# Main.net
KiCad netlist of a schematic drawn in Altium Designer
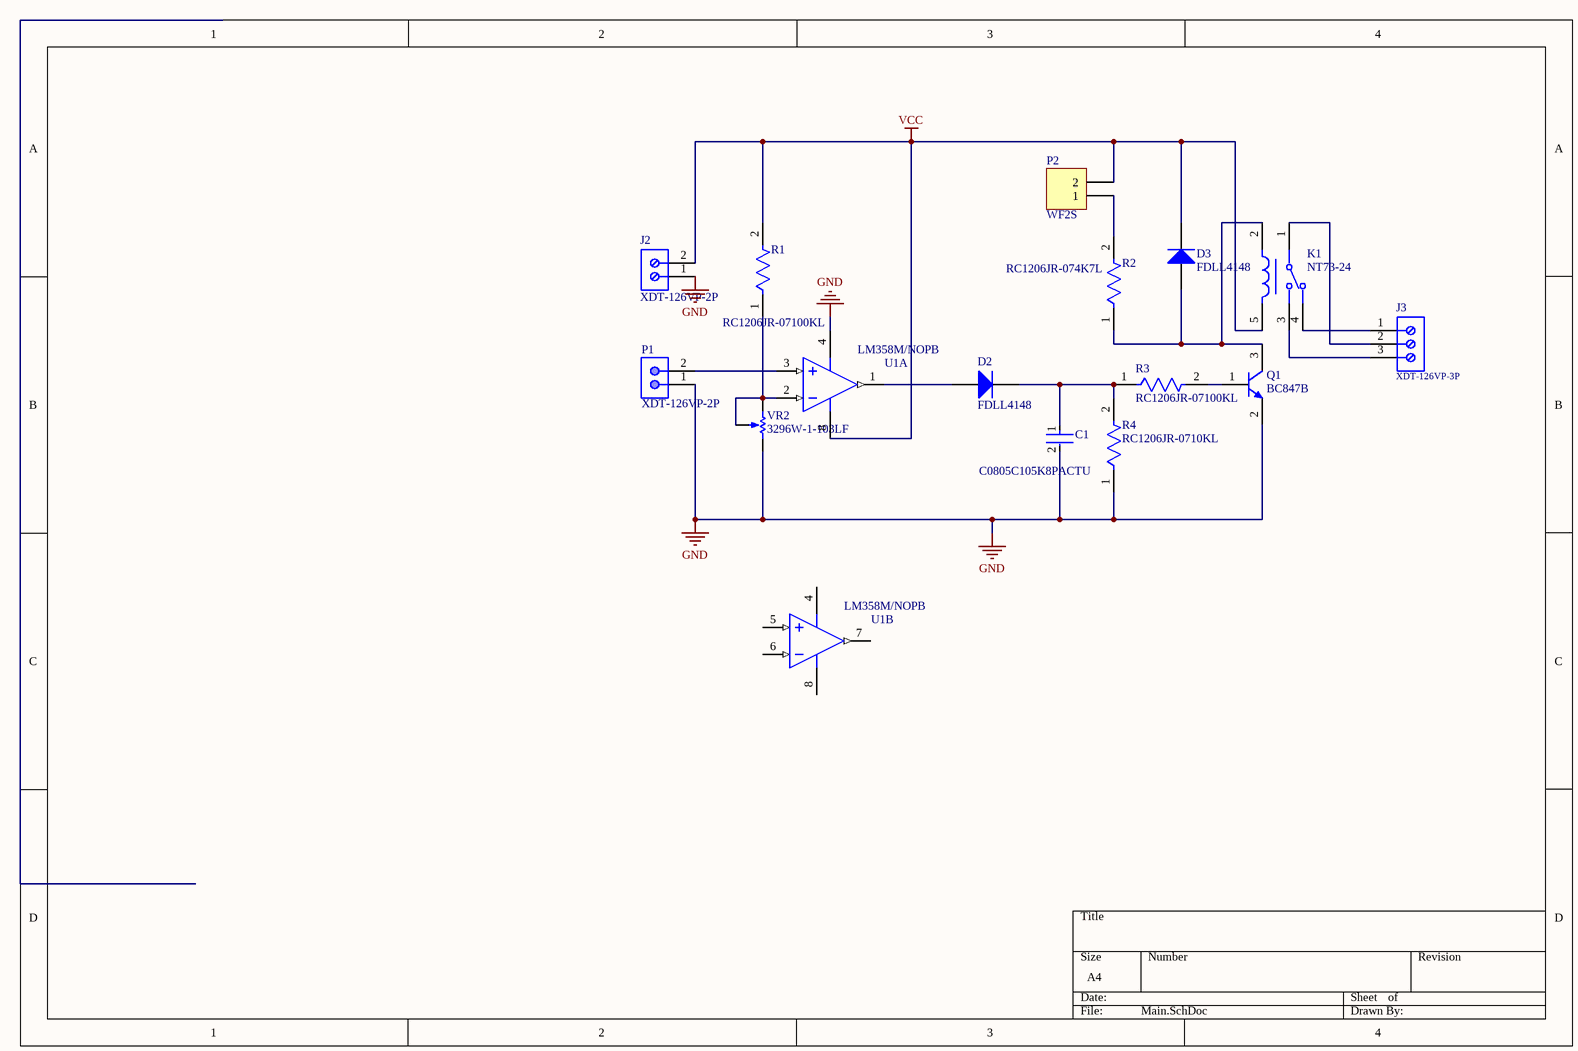
[diagram p0: Main.SchDoc]

(export (version "E")
  (design (tool "Eeschema 10.0.6"))
  (components
    (comp (ref "C1")
      (value "C0805C105K8PACTU")
      (footprint "FP-C0805C-DG-MFG")
      (description "CAP CER 1UF X5R 0805")
      (fields (field (name "TOLERANCE") "10%") (field (name "MANUFACTURER PART NUMBER") "C0805C106K8PACTU"))
      (libsource (lib "Altium Content Vault") (part "11868f565c42a9108669ba33697ecf6"))
    )
    (comp (ref "D2")
      (value "FDLL4148")
      (footprint "FAIR-LL-34_V")
      (description "High Conductance Fast Diode, 500 mW, 100 V, -65 to 175 degC, 2-Pin SMD, RoHS, Tape and Reel")
      (fields (field (name "MANUFACTURER") "FairchildSemiconductor"))
      (libsource (lib "Altium Content Vault") (part "D-AK-2"))
    )
    (comp (ref "D3")
      (value "FDLL4148")
      (footprint "FAIR-LL-34_V")
      (description "High Conductance Fast Diode, 500 mW, 100 V, -65 to 175 degC, 2-Pin SMD, RoHS, Tape and Reel")
      (fields (field (name "MANUFACTURER") "FairchildSemiconductor"))
      (libsource (lib "Altium Content Vault") (part "D-AK-2"))
    )
    (comp (ref "J2")
      (value "XDT-126VP-2P")
      (footprint "TECO-282836-2_V")
      (description "Female Header, Pitch 5 mm, 1 x 2 Position, Height 10 mm, Tail Length 3.5 mm, Rohs, Bulk")
      (fields (field (name "VOLTAGE") "300V") (field (name "MANUFACTURER") "TE Connectivity"))
      (libsource (lib "Altium Content Vault") (part "CN-1P-F-TB2"))
    )
    (comp (ref "J3")
      (value "XDT-126VP-3P")
      (footprint "691213710003")
      (description "Serie 213 - 5.00 mm Horizontal Entry Modular with RisingCage Clamp WR-TBL, 3 pin")
      (fields
        (field (name "MANUFACTURER") "Wurth Elektronik")
        (field (name "PART NUMBER") "691213710003")
        (field (name "PUBLISHER") "WurthElektronik")
      )
      (libsource (lib "Altium Content Vault") (part "WE-CN-1P-F-TB3"))
    )
    (comp (ref "K1")
      (value "NT73-24")
      (footprint "FP-JS1-5V-F-MFG")
      (description "RELAY GEN PURPOSE SPDT 10A 24V")
      (fields
        (field (name "MANUFACTURER PART NUMBER") "JS1-5V-F")
        (field (name "OCTOPART") "https://octopart.com/js1-5v-f-panasonic-39428621")
      )
      (libsource (lib "Altium Content Vault") (part "250623531296f86beaf95f2bc4a6d4c"))
    )
    (comp (ref "P1")
      (value "XDT-126VP-2P")
      (footprint "TECO-5-146280-2_V")
      (fields (field (name "MANUFACTURER") "TE Connectivity"))
      (libsource (lib "Altium Content Vault") (part "CN-1P-M-R2"))
    )
    (comp (ref "P2")
      (value "WF2S")
      (footprint "HDR1X2")
      (description "Header, 2-Pin")
      (fields (field (name "PUBLISHER") "Altium Limited"))
      (libsource (lib "Miscellaneous Connectors") (part "Header 2"))
    )
    (comp (ref "Q1")
      (value "BC847B")
      (footprint "INF-SOT23_L")
      (description "NPN Silicon AF Transistor, 45 V VCEO, 100 mA IC, SOT23, Reel, Green")
      (fields (field (name "MANUFACTURER") "Infineon"))
      (libsource (lib "Altium Content Vault") (part "INF-BJTNPN-BEC-3"))
    )
    (comp (ref "R1")
      (value "RC1206JR-07100KL")
      (footprint "FP-RC1206-MFG")
      (description "RES SMD 100 KOHM  1/4W 1206")
      (fields
        (field (name "MANUFACTURER PART NUMBER") "RC1206JR-070RL")
        (field (name "MANUFACTURER") "YAGEO")
      )
      (libsource (lib "Altium Content Vault") (part "1029c3af85768c4190bb7ad29bc67b5"))
    )
    (comp (ref "R2")
      (value "RC1206JR-074K7L")
      (footprint "FP-RC1206-MFG")
      (description "RES SMD 4700 OHM 1/4W 1206")
      (fields
        (field (name "MANUFACTURER PART NUMBER") "RC1206JR-070RL")
        (field (name "MANUFACTURER") "YAGEO")
      )
      (libsource (lib "Altium Content Vault") (part "1029c3af85768c4190bb7ad29bc67b5"))
    )
    (comp (ref "R3")
      (value "RC1206JR-07100KL")
      (footprint "FP-RC1206-MFG")
      (description "RES SMD 100 KOHM 1/4W 1206")
      (fields
        (field (name "MANUFACTURER PART NUMBER") "RC1206JR-070RL")
        (field (name "MANUFACTURER") "YAGEO")
      )
      (libsource (lib "Altium Content Vault") (part "1029c3af85768c4190bb7ad29bc67b5"))
    )
    (comp (ref "R4")
      (value "RC1206JR-0710KL")
      (footprint "FP-RC1206-MFG")
      (description "RES SMD 10 KOHM 1/4W 1206")
      (fields
        (field (name "MANUFACTURER PART NUMBER") "RC1206JR-070RL")
        (field (name "MANUFACTURER") "YAGEO")
      )
      (libsource (lib "Altium Content Vault") (part "1029c3af85768c4190bb7ad29bc67b5"))
    )
    (comp (ref "U1")
      (value "LM358M/NOPB")
      (footprint "D0008A_M")
      (description "Low Power Dual Operational Amplifier, 8-pin Narrow SOIC, Pb-Free")
      (fields (field (name "MANUFACTURER") "Texas Instruments"))
      (libsource (lib "Altium Content Vault") (part "AMP-OPA-LM158-8"))
    )
    (comp (ref "VR2")
      (value "3296W-1-103LF")
      (footprint "BOUR-3296W")
      (fields (field (name "TOLERANCE") "1%"))
      (libsource (lib "Altium Content Vault") (part "RES-POT-3"))
    )
  )
  (nets
    (net (code "1") (name "GND") (class "Default")
      (node (ref "C1") (pin "2") (pinfunction "2_2") (pintype "passive"))
      (node (ref "J2") (pin "1") (pinfunction "1_1") (pintype "passive"))
      (node (ref "P1") (pin "1") (pinfunction "1_1") (pintype "passive"))
      (node (ref "Q1") (pin "2") (pinfunction "E_2") (pintype "passive"))
      (node (ref "R4") (pin "1") (pinfunction "1_1") (pintype "passive"))
      (node (ref "U1") (pin "4") (pinfunction "GND_4") (pintype "power_in"))
      (node (ref "VR2") (pin "3") (pinfunction "CW_3") (pintype "passive"))
    )
    (net (code "2") (name "Net-(D2-A)") (class "Default")
      (node (ref "D2") (pin "1") (pinfunction "A_1") (pintype "passive"))
      (node (ref "U1") (pin "1") (pinfunction "OUTA_1") (pintype "output"))
    )
    (net (code "3") (name "Net-(D2-K)") (class "Default")
      (node (ref "C1") (pin "1") (pinfunction "1_1") (pintype "passive"))
      (node (ref "D2") (pin "2") (pinfunction "K_2") (pintype "passive"))
      (node (ref "R3") (pin "1") (pinfunction "1_1") (pintype "passive"))
      (node (ref "R4") (pin "2") (pinfunction "2_2") (pintype "passive"))
    )
    (net (code "4") (name "Net-(D3-A)") (class "Default")
      (node (ref "D3") (pin "1") (pinfunction "A_1") (pintype "passive"))
      (node (ref "K1") (pin "2") (pinfunction "1_COIL_2") (pintype "passive"))
      (node (ref "Q1") (pin "3") (pinfunction "C_3") (pintype "passive"))
      (node (ref "R2") (pin "1") (pinfunction "1_1") (pintype "passive"))
    )
    (net (code "5") (name "Net-(K1-COM)") (class "Default")
      (node (ref "J3") (pin "2") (pinfunction "2_2") (pintype "passive"))
      (node (ref "K1") (pin "1") (pinfunction "COM_1") (pintype "passive"))
    )
    (net (code "6") (name "Net-(K1-N.C.)") (class "Default")
      (node (ref "J3") (pin "1") (pinfunction "1_1") (pintype "passive"))
      (node (ref "K1") (pin "4") (pinfunction "N.C._4") (pintype "passive"))
    )
    (net (code "7") (name "Net-(K1-N.O.)") (class "Default")
      (node (ref "J3") (pin "3") (pinfunction "3_3") (pintype "passive"))
      (node (ref "K1") (pin "3") (pinfunction "N.O._3") (pintype "passive"))
    )
    (net (code "8") (name "Net-(P2-Pad1)") (class "Default")
      (node (ref "P2") (pin "1") (pinfunction "1_1") (pintype "passive"))
      (node (ref "R2") (pin "2") (pinfunction "2_2") (pintype "passive"))
    )
    (net (code "9") (name "Net-(Q1-B)") (class "Default")
      (node (ref "Q1") (pin "1") (pinfunction "B_1") (pintype "passive"))
      (node (ref "R3") (pin "2") (pinfunction "2_2") (pintype "passive"))
    )
    (net (code "10") (name "Net-(U1A-INA+)") (class "Default")
      (node (ref "P1") (pin "2") (pinfunction "2_2") (pintype "passive"))
      (node (ref "U1") (pin "3") (pinfunction "INA+_3") (pintype "input"))
    )
    (net (code "11") (name "Net-(U1A-INA-)") (class "Default")
      (node (ref "R1") (pin "1") (pinfunction "1_1") (pintype "passive"))
      (node (ref "U1") (pin "2") (pinfunction "INA-_2") (pintype "input"))
      (node (ref "VR2") (pin "1") (pinfunction "CCW_1") (pintype "passive"))
      (node (ref "VR2") (pin "2") (pinfunction "S_2") (pintype "passive"))
    )
    (net (code "12") (name "VCC") (class "Default")
      (node (ref "D3") (pin "2") (pinfunction "K_2") (pintype "passive"))
      (node (ref "J2") (pin "2") (pinfunction "2_2") (pintype "passive"))
      (node (ref "K1") (pin "5") (pinfunction "2_COIL_5") (pintype "passive"))
      (node (ref "P2") (pin "2") (pinfunction "2_2") (pintype "passive"))
      (node (ref "R1") (pin "2") (pinfunction "2_2") (pintype "passive"))
      (node (ref "U1") (pin "8") (pinfunction "V+_8") (pintype "power_in"))
    )
    (net (code "13") (name "unconnected-(U1B-GND-Pad4)") (class "Default")
      (node (ref "U1") (pin "4") (pinfunction "GND_4") (pintype "power_in"))
    )
    (net (code "14") (name "unconnected-(U1B-INB+-Pad5)") (class "Default")
      (node (ref "U1") (pin "5") (pinfunction "INB+_5") (pintype "input"))
    )
    (net (code "15") (name "unconnected-(U1B-INB--Pad6)") (class "Default")
      (node (ref "U1") (pin "6") (pinfunction "INB-_6") (pintype "input"))
    )
    (net (code "16") (name "unconnected-(U1B-OUTB-Pad7)") (class "Default")
      (node (ref "U1") (pin "7") (pinfunction "OUTB_7") (pintype "output"))
    )
    (net (code "17") (name "unconnected-(U1B-V+-Pad8)") (class "Default")
      (node (ref "U1") (pin "8") (pinfunction "V+_8") (pintype "power_in"))
    )
  )
)
